# RaspberryPi_Econet_Module_Adapter_-_Issu.net
KiCad netlist of a schematic drawn in EAGLE
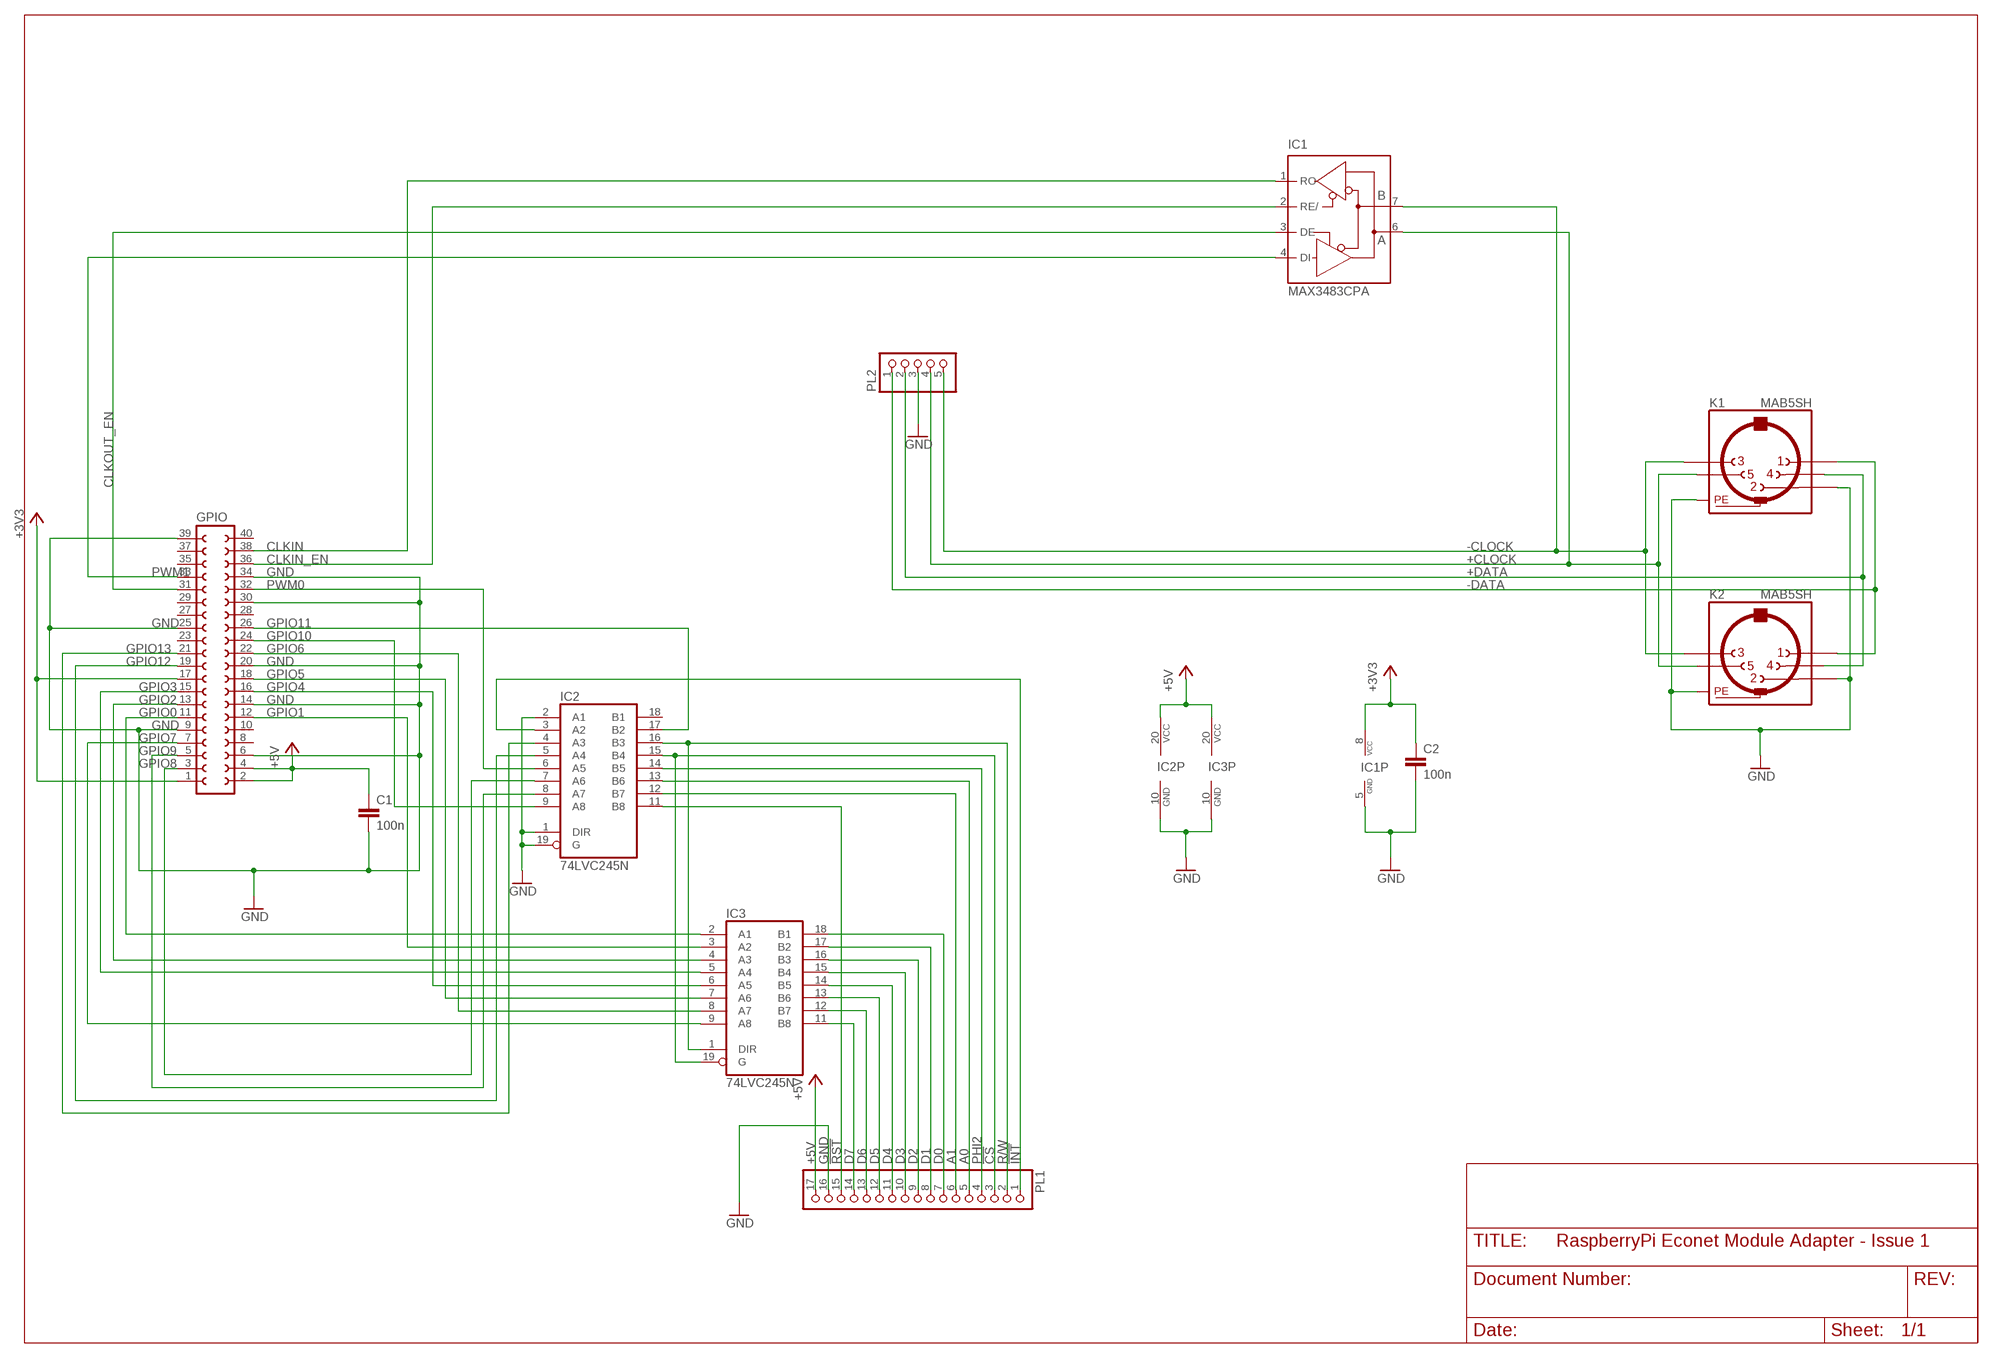
[diagram p0: schematic, sheet 1]

(export (version "E")
  (design (tool "Eeschema 10.0.6"))
  (components
    (comp (ref "C1")
      (value "100n")
      (footprint "eagle-import:C050-025X075")
      (libsource (lib "eagle-import") (part "C-EU050-025X075"))
    )
    (comp (ref "C2")
      (value "100n")
      (footprint "eagle-import:C050-025X075")
      (libsource (lib "eagle-import") (part "C-EU050-025X075"))
    )
    (comp (ref "GPIO")
      (value "FE20-2")
      (footprint "eagle-import:FE20-2")
      (libsource (lib "eagle-import") (part "FE20-2"))
    )
    (comp (ref "IC1")
      (value "MAX3483CPA")
      (footprint "eagle-import:DIL08")
      (fields (field (name "MPN") "MAX481CPA+"))
      (libsource (lib "eagle-import") (part "MAX481CPA"))
    )
    (comp (ref "IC2")
      (value "74LVC245N")
      (footprint "eagle-import:DIL20")
      (libsource (lib "eagle-import") (part "74245NLS"))
    )
    (comp (ref "IC3")
      (value "74LVC245N")
      (footprint "eagle-import:DIL20")
      (libsource (lib "eagle-import") (part "74245NLS"))
    )
    (comp (ref "K1")
      (value "MAB5SH")
      (footprint "eagle-import:MAB5SH")
      (libsource (lib "eagle-import") (part "MAB5SH"))
    )
    (comp (ref "K2")
      (value "MAB5SH")
      (footprint "eagle-import:MAB5SH")
      (libsource (lib "eagle-import") (part "MAB5SH"))
    )
    (comp (ref "PL1")
      (value "PINHD-1X17")
      (footprint "eagle-import:1X17")
      (libsource (lib "eagle-import") (part "PINHD-1X17"))
    )
    (comp (ref "PL2")
      (value "PINHD-1X5")
      (footprint "eagle-import:1X05")
      (libsource (lib "eagle-import") (part "PINHD-1X5"))
    )
  )
  (nets
    (net (code "1") (name "+3V3") (class "Default")
      (node (ref "C2") (pin "1") (pinfunction "1_1") (pintype "passive"))
      (node (ref "GPIO") (pin "1") (pinfunction "1_1") (pintype "passive"))
      (node (ref "GPIO") (pin "17") (pinfunction "17_17") (pintype "passive"))
      (node (ref "IC1") (pin "8") (pinfunction "VCC_8") (pintype "power_in"))
    )
    (net (code "2") (name "+5V") (class "Default")
      (node (ref "C1") (pin "1") (pinfunction "1_1") (pintype "passive"))
      (node (ref "GPIO") (pin "2") (pinfunction "2_2") (pintype "passive"))
      (node (ref "GPIO") (pin "4") (pinfunction "4_4") (pintype "passive"))
      (node (ref "IC2") (pin "20") (pinfunction "VCC_20") (pintype "power_in"))
      (node (ref "IC3") (pin "20") (pinfunction "VCC_20") (pintype "power_in"))
      (node (ref "PL1") (pin "17") (pinfunction "17_17") (pintype "passive"))
    )
    (net (code "3") (name "/+CLOCK") (class "Default")
      (node (ref "IC1") (pin "6") (pinfunction "A_6") (pintype "passive"))
      (node (ref "K1") (pin "5") (pinfunction "5_5") (pintype "passive"))
      (node (ref "K2") (pin "5") (pinfunction "5_5") (pintype "passive"))
      (node (ref "PL2") (pin "4") (pinfunction "4_4") (pintype "passive"))
    )
    (net (code "4") (name "/+DATA") (class "Default")
      (node (ref "K1") (pin "4") (pinfunction "4_4") (pintype "passive"))
      (node (ref "K2") (pin "4") (pinfunction "4_4") (pintype "passive"))
      (node (ref "PL2") (pin "2") (pinfunction "2_2") (pintype "passive"))
    )
    (net (code "5") (name "/-CLOCK") (class "Default")
      (node (ref "IC1") (pin "7") (pinfunction "B_7") (pintype "passive"))
      (node (ref "K1") (pin "3") (pinfunction "3_3") (pintype "passive"))
      (node (ref "K2") (pin "3") (pinfunction "3_3") (pintype "passive"))
      (node (ref "PL2") (pin "5") (pinfunction "5_5") (pintype "passive"))
    )
    (net (code "6") (name "/-DATA") (class "Default")
      (node (ref "K1") (pin "1") (pinfunction "1_1") (pintype "passive"))
      (node (ref "K2") (pin "1") (pinfunction "1_1") (pintype "passive"))
      (node (ref "PL2") (pin "1") (pinfunction "1_1") (pintype "passive"))
    )
    (net (code "7") (name "/A0") (class "Default")
      (node (ref "IC2") (pin "13") (pinfunction "B6_13") (pintype "bidirectional"))
      (node (ref "PL1") (pin "5") (pinfunction "5_5") (pintype "passive"))
    )
    (net (code "8") (name "/A1") (class "Default")
      (node (ref "IC2") (pin "12") (pinfunction "B7_12") (pintype "bidirectional"))
      (node (ref "PL1") (pin "6") (pinfunction "6_6") (pintype "passive"))
    )
    (net (code "9") (name "/CLKIN") (class "Default")
      (node (ref "GPIO") (pin "38") (pinfunction "38_38") (pintype "passive"))
      (node (ref "IC1") (pin "1") (pinfunction "RO_1") (pintype "output"))
    )
    (net (code "10") (name "/CLKIN_EN") (class "Default")
      (node (ref "GPIO") (pin "36") (pinfunction "36_36") (pintype "passive"))
      (node (ref "IC1") (pin "2") (pinfunction "RE/_2") (pintype "input"))
    )
    (net (code "11") (name "/CLKOUT_EN") (class "Default")
      (node (ref "GPIO") (pin "31") (pinfunction "31_31") (pintype "passive"))
      (node (ref "IC1") (pin "3") (pinfunction "DE_3") (pintype "input"))
    )
    (net (code "12") (name "/D0") (class "Default")
      (node (ref "IC3") (pin "18") (pinfunction "B1_18") (pintype "bidirectional"))
      (node (ref "PL1") (pin "7") (pinfunction "7_7") (pintype "passive"))
    )
    (net (code "13") (name "/D1") (class "Default")
      (node (ref "IC3") (pin "17") (pinfunction "B2_17") (pintype "bidirectional"))
      (node (ref "PL1") (pin "8") (pinfunction "8_8") (pintype "passive"))
    )
    (net (code "14") (name "/D2") (class "Default")
      (node (ref "IC3") (pin "16") (pinfunction "B3_16") (pintype "bidirectional"))
      (node (ref "PL1") (pin "9") (pinfunction "9_9") (pintype "passive"))
    )
    (net (code "15") (name "/D3") (class "Default")
      (node (ref "IC3") (pin "15") (pinfunction "B4_15") (pintype "bidirectional"))
      (node (ref "PL1") (pin "10") (pinfunction "10_10") (pintype "passive"))
    )
    (net (code "16") (name "/D4") (class "Default")
      (node (ref "IC3") (pin "14") (pinfunction "B5_14") (pintype "bidirectional"))
      (node (ref "PL1") (pin "11") (pinfunction "11_11") (pintype "passive"))
    )
    (net (code "17") (name "/D5") (class "Default")
      (node (ref "IC3") (pin "13") (pinfunction "B6_13") (pintype "bidirectional"))
      (node (ref "PL1") (pin "12") (pinfunction "12_12") (pintype "passive"))
    )
    (net (code "18") (name "/D6") (class "Default")
      (node (ref "IC3") (pin "12") (pinfunction "B7_12") (pintype "bidirectional"))
      (node (ref "PL1") (pin "13") (pinfunction "13_13") (pintype "passive"))
    )
    (net (code "19") (name "/D7") (class "Default")
      (node (ref "IC3") (pin "11") (pinfunction "B8_11") (pintype "bidirectional"))
      (node (ref "PL1") (pin "14") (pinfunction "14_14") (pintype "passive"))
    )
    (net (code "20") (name "/GPIO0") (class "Default")
      (node (ref "GPIO") (pin "11") (pinfunction "11_11") (pintype "passive"))
      (node (ref "IC3") (pin "2") (pinfunction "A1_2") (pintype "bidirectional"))
    )
    (net (code "21") (name "/GPIO1") (class "Default")
      (node (ref "GPIO") (pin "12") (pinfunction "12_12") (pintype "passive"))
      (node (ref "IC3") (pin "3") (pinfunction "A2_3") (pintype "bidirectional"))
    )
    (net (code "22") (name "/GPIO2") (class "Default")
      (node (ref "GPIO") (pin "13") (pinfunction "13_13") (pintype "passive"))
      (node (ref "IC3") (pin "4") (pinfunction "A3_4") (pintype "bidirectional"))
    )
    (net (code "23") (name "/GPIO3") (class "Default")
      (node (ref "GPIO") (pin "15") (pinfunction "15_15") (pintype "passive"))
      (node (ref "IC3") (pin "5") (pinfunction "A4_5") (pintype "bidirectional"))
    )
    (net (code "24") (name "/GPIO4") (class "Default")
      (node (ref "GPIO") (pin "16") (pinfunction "16_16") (pintype "passive"))
      (node (ref "IC3") (pin "6") (pinfunction "A5_6") (pintype "bidirectional"))
    )
    (net (code "25") (name "/GPIO5") (class "Default")
      (node (ref "GPIO") (pin "18") (pinfunction "18_18") (pintype "passive"))
      (node (ref "IC3") (pin "7") (pinfunction "A6_7") (pintype "bidirectional"))
    )
    (net (code "26") (name "/GPIO6") (class "Default")
      (node (ref "GPIO") (pin "22") (pinfunction "22_22") (pintype "passive"))
      (node (ref "IC3") (pin "8") (pinfunction "A7_8") (pintype "bidirectional"))
    )
    (net (code "27") (name "/GPIO7") (class "Default")
      (node (ref "GPIO") (pin "7") (pinfunction "7_7") (pintype "passive"))
      (node (ref "IC3") (pin "9") (pinfunction "A8_9") (pintype "bidirectional"))
    )
    (net (code "28") (name "/GPIO8") (class "Default")
      (node (ref "GPIO") (pin "3") (pinfunction "3_3") (pintype "passive"))
      (node (ref "IC2") (pin "7") (pinfunction "A6_7") (pintype "bidirectional"))
    )
    (net (code "29") (name "/GPIO9") (class "Default")
      (node (ref "GPIO") (pin "5") (pinfunction "5_5") (pintype "passive"))
      (node (ref "IC2") (pin "8") (pinfunction "A7_8") (pintype "bidirectional"))
    )
    (net (code "30") (name "/GPIO10") (class "Default")
      (node (ref "GPIO") (pin "24") (pinfunction "24_24") (pintype "passive"))
      (node (ref "IC2") (pin "9") (pinfunction "A8_9") (pintype "bidirectional"))
    )
    (net (code "31") (name "/GPIO11") (class "Default")
      (node (ref "GPIO") (pin "26") (pinfunction "26_26") (pintype "passive"))
      (node (ref "IC2") (pin "17") (pinfunction "B2_17") (pintype "bidirectional"))
    )
    (net (code "32") (name "/GPIO12") (class "Default")
      (node (ref "GPIO") (pin "19") (pinfunction "19_19") (pintype "passive"))
      (node (ref "IC2") (pin "5") (pinfunction "A4_5") (pintype "bidirectional"))
    )
    (net (code "33") (name "/GPIO13") (class "Default")
      (node (ref "GPIO") (pin "21") (pinfunction "21_21") (pintype "passive"))
      (node (ref "IC2") (pin "4") (pinfunction "A3_4") (pintype "bidirectional"))
    )
    (net (code "34") (name "/PHI2") (class "Default")
      (node (ref "IC2") (pin "14") (pinfunction "B5_14") (pintype "bidirectional"))
      (node (ref "PL1") (pin "4") (pinfunction "4_4") (pintype "passive"))
    )
    (net (code "35") (name "/PWM0") (class "Default")
      (node (ref "GPIO") (pin "32") (pinfunction "32_32") (pintype "passive"))
      (node (ref "IC2") (pin "6") (pinfunction "A5_6") (pintype "bidirectional"))
    )
    (net (code "36") (name "/PWM1") (class "Default")
      (node (ref "GPIO") (pin "33") (pinfunction "33_33") (pintype "passive"))
      (node (ref "IC1") (pin "4") (pinfunction "DI_4") (pintype "input"))
    )
    (net (code "37") (name "/R{slash}W") (class "Default")
      (node (ref "IC2") (pin "16") (pinfunction "B3_16") (pintype "bidirectional"))
      (node (ref "IC3") (pin "1") (pinfunction "DIR_1") (pintype "input"))
      (node (ref "PL1") (pin "2") (pinfunction "2_2") (pintype "passive"))
    )
    (net (code "38") (name "/~{CS}") (class "Default")
      (node (ref "IC2") (pin "15") (pinfunction "B4_15") (pintype "bidirectional"))
      (node (ref "IC3") (pin "19") (pinfunction "G_19") (pintype "input"))
      (node (ref "PL1") (pin "3") (pinfunction "3_3") (pintype "passive"))
    )
    (net (code "39") (name "/~{INT}") (class "Default")
      (node (ref "IC2") (pin "3") (pinfunction "A2_3") (pintype "bidirectional"))
      (node (ref "PL1") (pin "1") (pinfunction "1_1") (pintype "passive"))
    )
    (net (code "40") (name "/~{RST}") (class "Default")
      (node (ref "IC2") (pin "11") (pinfunction "B8_11") (pintype "bidirectional"))
      (node (ref "PL1") (pin "15") (pinfunction "15_15") (pintype "passive"))
    )
    (net (code "41") (name "GND") (class "Default")
      (node (ref "C1") (pin "2") (pinfunction "2_2") (pintype "passive"))
      (node (ref "C2") (pin "2") (pinfunction "2_2") (pintype "passive"))
      (node (ref "GPIO") (pin "14") (pinfunction "14_14") (pintype "passive"))
      (node (ref "GPIO") (pin "20") (pinfunction "20_20") (pintype "passive"))
      (node (ref "GPIO") (pin "25") (pinfunction "25_25") (pintype "passive"))
      (node (ref "GPIO") (pin "30") (pinfunction "30_30") (pintype "passive"))
      (node (ref "GPIO") (pin "34") (pinfunction "34_34") (pintype "passive"))
      (node (ref "GPIO") (pin "39") (pinfunction "39_39") (pintype "passive"))
      (node (ref "GPIO") (pin "6") (pinfunction "6_6") (pintype "passive"))
      (node (ref "GPIO") (pin "9") (pinfunction "9_9") (pintype "passive"))
      (node (ref "IC1") (pin "5") (pinfunction "GND_5") (pintype "power_in"))
      (node (ref "IC2") (pin "1") (pinfunction "DIR_1") (pintype "input"))
      (node (ref "IC2") (pin "10") (pinfunction "GND_10") (pintype "power_in"))
      (node (ref "IC2") (pin "19") (pinfunction "G_19") (pintype "input"))
      (node (ref "IC2") (pin "2") (pinfunction "A1_2") (pintype "bidirectional"))
      (node (ref "IC3") (pin "10") (pinfunction "GND_10") (pintype "power_in"))
      (node (ref "K1") (pin "2") (pinfunction "2_2") (pintype "passive"))
      (node (ref "K1") (pin "PE") (pinfunction "PE_PE") (pintype "power_in"))
      (node (ref "K1") (pin "PE@") (pinfunction "PE_PE@") (pintype "power_in"))
      (node (ref "K2") (pin "2") (pinfunction "2_2") (pintype "passive"))
      (node (ref "K2") (pin "PE") (pinfunction "PE_PE") (pintype "power_in"))
      (node (ref "K2") (pin "PE@") (pinfunction "PE_PE@") (pintype "power_in"))
      (node (ref "PL1") (pin "16") (pinfunction "16_16") (pintype "passive"))
      (node (ref "PL2") (pin "3") (pinfunction "3_3") (pintype "passive"))
    )
    (net (code "42") (name "unconnected-(GPIO-Pad8)") (class "Default")
      (node (ref "GPIO") (pin "8") (pinfunction "8_8") (pintype "passive"))
    )
    (net (code "43") (name "unconnected-(GPIO-Pad10)") (class "Default")
      (node (ref "GPIO") (pin "10") (pinfunction "10_10") (pintype "passive"))
    )
    (net (code "44") (name "unconnected-(GPIO-Pad23)") (class "Default")
      (node (ref "GPIO") (pin "23") (pinfunction "23_23") (pintype "passive"))
    )
    (net (code "45") (name "unconnected-(GPIO-Pad27)") (class "Default")
      (node (ref "GPIO") (pin "27") (pinfunction "27_27") (pintype "passive"))
    )
    (net (code "46") (name "unconnected-(GPIO-Pad28)") (class "Default")
      (node (ref "GPIO") (pin "28") (pinfunction "28_28") (pintype "passive"))
    )
    (net (code "47") (name "unconnected-(GPIO-Pad29)") (class "Default")
      (node (ref "GPIO") (pin "29") (pinfunction "29_29") (pintype "passive"))
    )
    (net (code "48") (name "unconnected-(GPIO-Pad35)") (class "Default")
      (node (ref "GPIO") (pin "35") (pinfunction "35_35") (pintype "passive"))
    )
    (net (code "49") (name "unconnected-(GPIO-Pad37)") (class "Default")
      (node (ref "GPIO") (pin "37") (pinfunction "37_37") (pintype "passive"))
    )
    (net (code "50") (name "unconnected-(GPIO-Pad40)") (class "Default")
      (node (ref "GPIO") (pin "40") (pinfunction "40_40") (pintype "passive"))
    )
    (net (code "51") (name "unconnected-(IC2A-B1-Pad18)") (class "Default")
      (node (ref "IC2") (pin "18") (pinfunction "B1_18") (pintype "bidirectional"))
    )
  )
)
